# IR_detector_perf.net
KiCad netlist of a schematic drawn in EAGLE
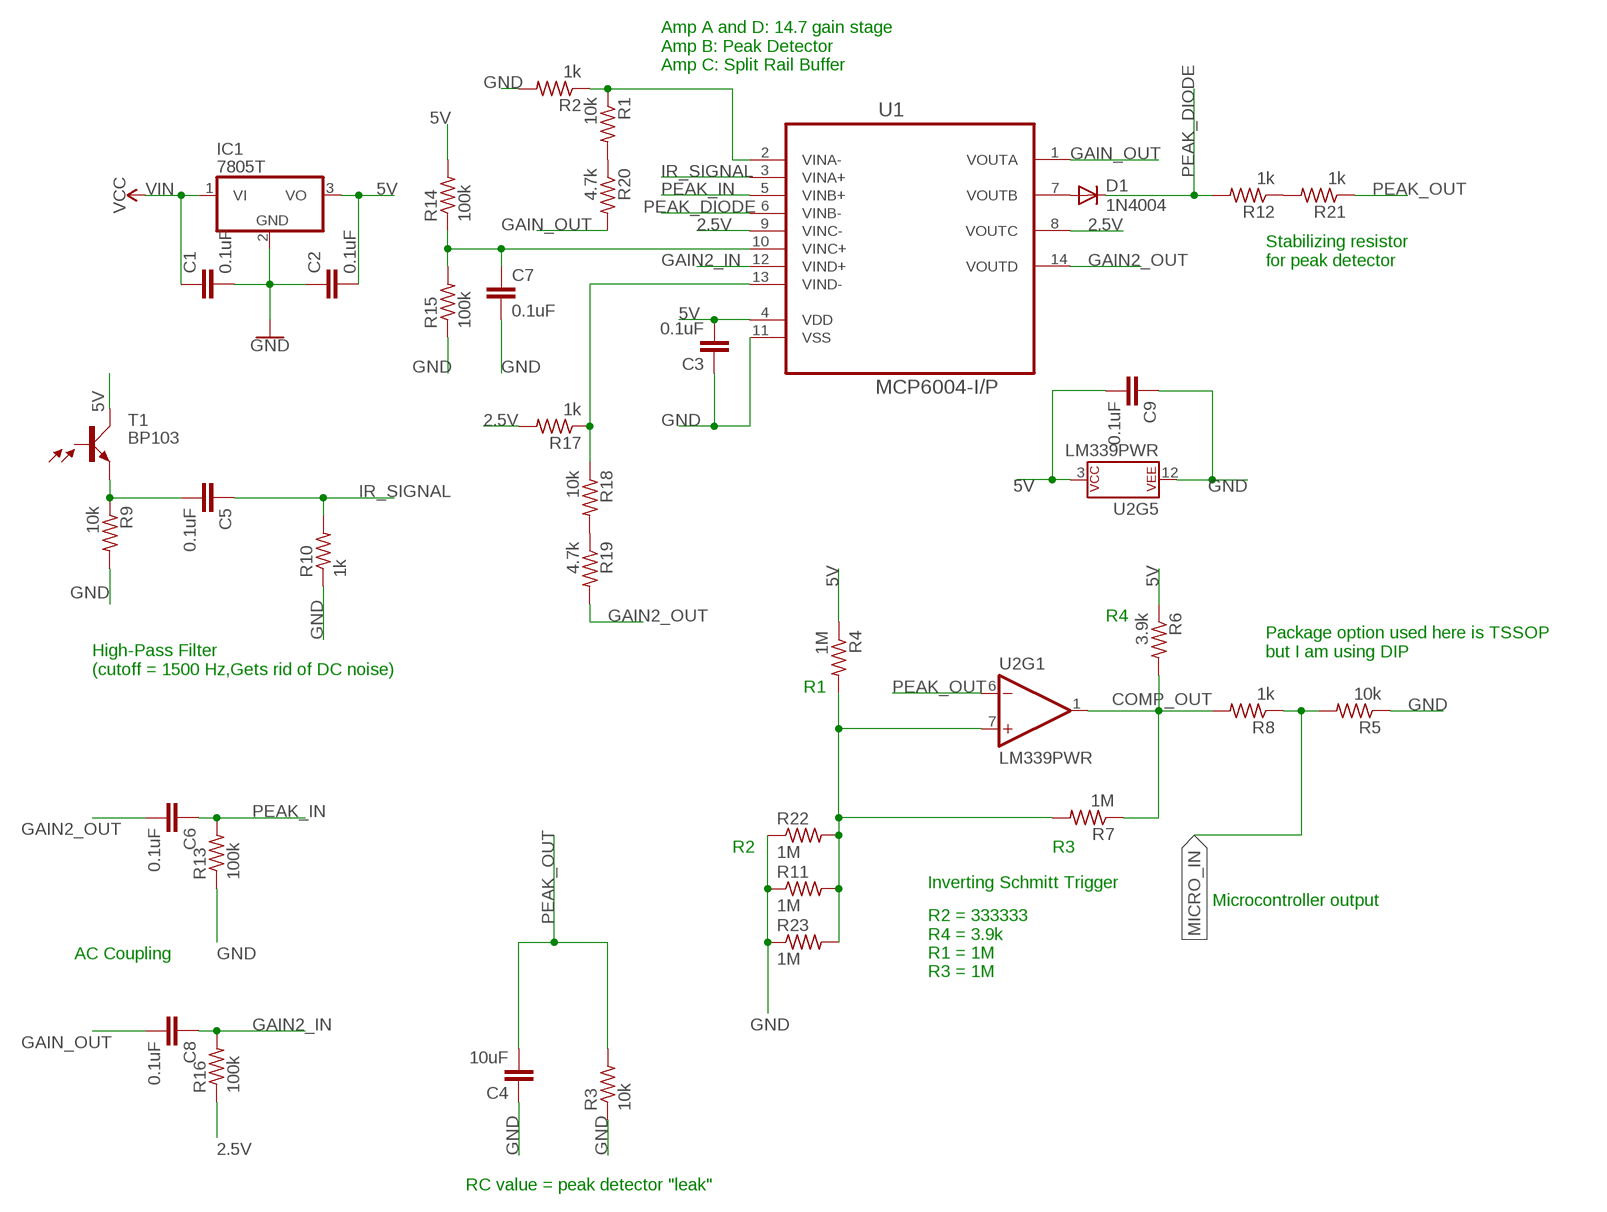
[diagram p0: schematic, sheet 1]

(export (version "E")
  (design (tool "Eeschema 10.0.6"))
  (components
    (comp (ref "C1")
      (value "0.1uF")
      (footprint "eagle-import:C025-024X044")
      (libsource (lib "eagle-import") (part "C-EU025-024X044"))
    )
    (comp (ref "C2")
      (value "0.1uF")
      (footprint "eagle-import:C025-024X044")
      (libsource (lib "eagle-import") (part "C-EU025-024X044"))
    )
    (comp (ref "C3")
      (value "0.1uF")
      (footprint "eagle-import:C025-024X044")
      (libsource (lib "eagle-import") (part "C-EU025-024X044"))
    )
    (comp (ref "C4")
      (value "10uF")
      (footprint "eagle-import:C025-024X044")
      (libsource (lib "eagle-import") (part "C-EU025-024X044"))
    )
    (comp (ref "C5")
      (value "0.1uF")
      (footprint "eagle-import:C025-024X044")
      (libsource (lib "eagle-import") (part "C-EU025-024X044"))
    )
    (comp (ref "C6")
      (value "0.1uF")
      (footprint "eagle-import:C025-024X044")
      (libsource (lib "eagle-import") (part "C-EU025-024X044"))
    )
    (comp (ref "C7")
      (value "0.1uF")
      (footprint "eagle-import:C025-024X044")
      (libsource (lib "eagle-import") (part "C-EU025-024X044"))
    )
    (comp (ref "C8")
      (value "0.1uF")
      (footprint "eagle-import:C025-024X044")
      (libsource (lib "eagle-import") (part "C-EU025-024X044"))
    )
    (comp (ref "C9")
      (value "0.1uF")
      (footprint "eagle-import:C025-024X044")
      (libsource (lib "eagle-import") (part "C-EU025-024X044"))
    )
    (comp (ref "D1")
      (value "1N4004")
      (footprint "eagle-import:DO41-10")
      (libsource (lib "eagle-import") (part "1N4004"))
    )
    (comp (ref "IC1")
      (value "7805T")
      (footprint "eagle-import:TO220H")
      (libsource (lib "eagle-import") (part "78T05"))
    )
    (comp (ref "R1")
      (value "10k")
      (footprint "eagle-import:0204V")
      (libsource (lib "eagle-import") (part "R-US_0204/2V"))
    )
    (comp (ref "R2")
      (value "1k")
      (footprint "eagle-import:0204V")
      (libsource (lib "eagle-import") (part "R-US_0204/2V"))
    )
    (comp (ref "R3")
      (value "10k")
      (footprint "eagle-import:0204V")
      (libsource (lib "eagle-import") (part "R-US_0204/2V"))
    )
    (comp (ref "R4")
      (value "1M")
      (footprint "eagle-import:0204V")
      (libsource (lib "eagle-import") (part "R-US_0204/2V"))
    )
    (comp (ref "R5")
      (value "10k")
      (footprint "eagle-import:0204V")
      (libsource (lib "eagle-import") (part "R-US_0204/2V"))
    )
    (comp (ref "R6")
      (value "3.9k")
      (footprint "eagle-import:0204V")
      (libsource (lib "eagle-import") (part "R-US_0204/2V"))
    )
    (comp (ref "R7")
      (value "1M")
      (footprint "eagle-import:0204V")
      (libsource (lib "eagle-import") (part "R-US_0204/2V"))
    )
    (comp (ref "R8")
      (value "1k")
      (footprint "eagle-import:0204V")
      (libsource (lib "eagle-import") (part "R-US_0204/2V"))
    )
    (comp (ref "R9")
      (value "10k")
      (footprint "eagle-import:0204V")
      (libsource (lib "eagle-import") (part "R-US_0204/2V"))
    )
    (comp (ref "R10")
      (value "1k")
      (footprint "eagle-import:0204V")
      (libsource (lib "eagle-import") (part "R-US_0204/2V"))
    )
    (comp (ref "R11")
      (value "1M")
      (footprint "eagle-import:0204V")
      (libsource (lib "eagle-import") (part "R-US_0204/2V"))
    )
    (comp (ref "R12")
      (value "1k")
      (footprint "eagle-import:0204V")
      (libsource (lib "eagle-import") (part "R-US_0204/2V"))
    )
    (comp (ref "R13")
      (value "100k")
      (footprint "eagle-import:0204V")
      (libsource (lib "eagle-import") (part "R-US_0204/2V"))
    )
    (comp (ref "R14")
      (value "100k")
      (footprint "eagle-import:0204V")
      (libsource (lib "eagle-import") (part "R-US_0204/2V"))
    )
    (comp (ref "R15")
      (value "100k")
      (footprint "eagle-import:0204V")
      (libsource (lib "eagle-import") (part "R-US_0204/2V"))
    )
    (comp (ref "R16")
      (value "100k")
      (footprint "eagle-import:0204V")
      (libsource (lib "eagle-import") (part "R-US_0204/2V"))
    )
    (comp (ref "R17")
      (value "1k")
      (footprint "eagle-import:0204V")
      (libsource (lib "eagle-import") (part "R-US_0204/2V"))
    )
    (comp (ref "R18")
      (value "10k")
      (footprint "eagle-import:0204V")
      (libsource (lib "eagle-import") (part "R-US_0204/2V"))
    )
    (comp (ref "R19")
      (value "4.7k")
      (footprint "eagle-import:0204V")
      (libsource (lib "eagle-import") (part "R-US_0204/2V"))
    )
    (comp (ref "R20")
      (value "4.7k")
      (footprint "eagle-import:0204V")
      (libsource (lib "eagle-import") (part "R-US_0204/2V"))
    )
    (comp (ref "R21")
      (value "1k")
      (footprint "eagle-import:0204V")
      (libsource (lib "eagle-import") (part "R-US_0204/2V"))
    )
    (comp (ref "R22")
      (value "1M")
      (footprint "eagle-import:0204V")
      (libsource (lib "eagle-import") (part "R-US_0204/2V"))
    )
    (comp (ref "R23")
      (value "1M")
      (footprint "eagle-import:0204V")
      (libsource (lib "eagle-import") (part "R-US_0204/2V"))
    )
    (comp (ref "T1")
      (value "BP103")
      (footprint "eagle-import:BP103")
      (libsource (lib "eagle-import") (part "BP103"))
    )
    (comp (ref "U1")
      (value "MCP6004-I/P")
      (footprint "eagle-import:DIP254P762X533-14")
      (libsource (lib "eagle-import") (part "MCP6004-I/P"))
    )
    (comp (ref "U2")
      (value "LM339PWR")
      (footprint "eagle-import:TSSOP-14")
      (libsource (lib "eagle-import") (part "LM339"))
    )
  )
  (nets
    (net (code "1") (name "/2.5V") (class "Default")
      (node (ref "R16") (pin "1") (pinfunction "1_1") (pintype "passive"))
      (node (ref "R17") (pin "2") (pinfunction "2_2") (pintype "passive"))
      (node (ref "U1") (pin "8") (pinfunction "VOUTC_8") (pintype "output"))
      (node (ref "U1") (pin "9") (pinfunction "VINC-_9") (pintype "input"))
    )
    (net (code "2") (name "/5V") (class "Default")
      (node (ref "C2") (pin "2") (pinfunction "2_2") (pintype "passive"))
      (node (ref "C3") (pin "2") (pinfunction "2_2") (pintype "passive"))
      (node (ref "C9") (pin "2") (pinfunction "2_2") (pintype "passive"))
      (node (ref "IC1") (pin "3") (pinfunction "VO_3") (pintype "passive"))
      (node (ref "R14") (pin "2") (pinfunction "2_2") (pintype "passive"))
      (node (ref "R4") (pin "1") (pinfunction "1_1") (pintype "passive"))
      (node (ref "R6") (pin "1") (pinfunction "1_1") (pintype "passive"))
      (node (ref "T1") (pin "C") (pinfunction "C_C") (pintype "passive"))
      (node (ref "U1") (pin "4") (pinfunction "VDD_4") (pintype "power_in"))
      (node (ref "U2") (pin "3") (pinfunction "P$V+_3") (pintype "bidirectional"))
    )
    (net (code "3") (name "/COMP_OUT") (class "Default")
      (node (ref "R6") (pin "2") (pinfunction "2_2") (pintype "passive"))
      (node (ref "R7") (pin "1") (pinfunction "1_1") (pintype "passive"))
      (node (ref "R8") (pin "2") (pinfunction "2_2") (pintype "passive"))
      (node (ref "U2") (pin "1") (pinfunction "OUT_1") (pintype "output"))
    )
    (net (code "4") (name "/GAIN2_IN") (class "Default")
      (node (ref "C8") (pin "1") (pinfunction "1_1") (pintype "passive"))
      (node (ref "R16") (pin "2") (pinfunction "2_2") (pintype "passive"))
      (node (ref "U1") (pin "12") (pinfunction "VIND+_12") (pintype "input"))
    )
    (net (code "5") (name "/GAIN2_OUT") (class "Default")
      (node (ref "C6") (pin "2") (pinfunction "2_2") (pintype "passive"))
      (node (ref "R19") (pin "2") (pinfunction "2_2") (pintype "passive"))
      (node (ref "U1") (pin "14") (pinfunction "VOUTD_14") (pintype "output"))
    )
    (net (code "6") (name "/GAIN_OUT") (class "Default")
      (node (ref "C8") (pin "2") (pinfunction "2_2") (pintype "passive"))
      (node (ref "R20") (pin "2") (pinfunction "2_2") (pintype "passive"))
      (node (ref "U1") (pin "1") (pinfunction "VOUTA_1") (pintype "output"))
    )
    (net (code "7") (name "/IR_SIGNAL") (class "Default")
      (node (ref "C5") (pin "1") (pinfunction "1_1") (pintype "passive"))
      (node (ref "R10") (pin "2") (pinfunction "2_2") (pintype "passive"))
      (node (ref "U1") (pin "3") (pinfunction "VINA+_3") (pintype "input"))
    )
    (net (code "8") (name "/PEAK_DIODE") (class "Default")
      (node (ref "D1") (pin "C") (pinfunction "C_C") (pintype "passive"))
      (node (ref "R12") (pin "2") (pinfunction "2_2") (pintype "passive"))
      (node (ref "U1") (pin "6") (pinfunction "VINB-_6") (pintype "input"))
    )
    (net (code "9") (name "/PEAK_IN") (class "Default")
      (node (ref "C6") (pin "1") (pinfunction "1_1") (pintype "passive"))
      (node (ref "R13") (pin "2") (pinfunction "2_2") (pintype "passive"))
      (node (ref "U1") (pin "5") (pinfunction "VINB+_5") (pintype "input"))
    )
    (net (code "10") (name "/PEAK_OUT") (class "Default")
      (node (ref "C4") (pin "2") (pinfunction "2_2") (pintype "passive"))
      (node (ref "R21") (pin "1") (pinfunction "1_1") (pintype "passive"))
      (node (ref "R3") (pin "2") (pinfunction "2_2") (pintype "passive"))
      (node (ref "U2") (pin "6") (pinfunction "-IN_6") (pintype "input"))
    )
    (net (code "11") (name "GND") (class "Default")
      (node (ref "C1") (pin "2") (pinfunction "2_2") (pintype "passive"))
      (node (ref "C2") (pin "1") (pinfunction "1_1") (pintype "passive"))
      (node (ref "C3") (pin "1") (pinfunction "1_1") (pintype "passive"))
      (node (ref "C4") (pin "1") (pinfunction "1_1") (pintype "passive"))
      (node (ref "C7") (pin "2") (pinfunction "2_2") (pintype "passive"))
      (node (ref "C9") (pin "1") (pinfunction "1_1") (pintype "passive"))
      (node (ref "IC1") (pin "2") (pinfunction "GND_2") (pintype "passive"))
      (node (ref "R10") (pin "1") (pinfunction "1_1") (pintype "passive"))
      (node (ref "R11") (pin "1") (pinfunction "1_1") (pintype "passive"))
      (node (ref "R13") (pin "1") (pinfunction "1_1") (pintype "passive"))
      (node (ref "R15") (pin "1") (pinfunction "1_1") (pintype "passive"))
      (node (ref "R2") (pin "2") (pinfunction "2_2") (pintype "passive"))
      (node (ref "R22") (pin "1") (pinfunction "1_1") (pintype "passive"))
      (node (ref "R23") (pin "1") (pinfunction "1_1") (pintype "passive"))
      (node (ref "R3") (pin "1") (pinfunction "1_1") (pintype "passive"))
      (node (ref "R5") (pin "1") (pinfunction "1_1") (pintype "passive"))
      (node (ref "R9") (pin "2") (pinfunction "2_2") (pintype "passive"))
      (node (ref "U1") (pin "11") (pinfunction "VSS_11") (pintype "passive"))
      (node (ref "U2") (pin "12") (pinfunction "P$V-_12") (pintype "bidirectional"))
    )
    (net (code "12") (name "MICRO_IN") (class "Default")
      (node (ref "R5") (pin "2") (pinfunction "2_2") (pintype "passive"))
      (node (ref "R8") (pin "1") (pinfunction "1_1") (pintype "passive"))
    )
    (net (code "13") (name "Net-(C5-Pad2)") (class "Default")
      (node (ref "C5") (pin "2") (pinfunction "2_2") (pintype "passive"))
      (node (ref "R9") (pin "1") (pinfunction "1_1") (pintype "passive"))
      (node (ref "T1") (pin "E") (pinfunction "E_E") (pintype "passive"))
    )
    (net (code "14") (name "Net-(R1-Pad2)") (class "Default")
      (node (ref "R1") (pin "2") (pinfunction "2_2") (pintype "passive"))
      (node (ref "R20") (pin "1") (pinfunction "1_1") (pintype "passive"))
    )
    (net (code "15") (name "Net-(R12-Pad1)") (class "Default")
      (node (ref "R12") (pin "1") (pinfunction "1_1") (pintype "passive"))
      (node (ref "R21") (pin "2") (pinfunction "2_2") (pintype "passive"))
    )
    (net (code "16") (name "Net-(R18-Pad2)") (class "Default")
      (node (ref "R18") (pin "2") (pinfunction "2_2") (pintype "passive"))
      (node (ref "R19") (pin "1") (pinfunction "1_1") (pintype "passive"))
    )
    (net (code "17") (name "Net-(U1-VINA-)") (class "Default")
      (node (ref "R1") (pin "1") (pinfunction "1_1") (pintype "passive"))
      (node (ref "R2") (pin "1") (pinfunction "1_1") (pintype "passive"))
      (node (ref "U1") (pin "2") (pinfunction "VINA-_2") (pintype "input"))
    )
    (net (code "18") (name "Net-(U1-VINC+)") (class "Default")
      (node (ref "C7") (pin "1") (pinfunction "1_1") (pintype "passive"))
      (node (ref "R14") (pin "1") (pinfunction "1_1") (pintype "passive"))
      (node (ref "R15") (pin "2") (pinfunction "2_2") (pintype "passive"))
      (node (ref "U1") (pin "10") (pinfunction "VINC+_10") (pintype "input"))
    )
    (net (code "19") (name "Net-(U1-VIND-)") (class "Default")
      (node (ref "R17") (pin "1") (pinfunction "1_1") (pintype "passive"))
      (node (ref "R18") (pin "1") (pinfunction "1_1") (pintype "passive"))
      (node (ref "U1") (pin "13") (pinfunction "VIND-_13") (pintype "input"))
    )
    (net (code "20") (name "Net-(U1-VOUTB)") (class "Default")
      (node (ref "D1") (pin "A") (pinfunction "A_A") (pintype "passive"))
      (node (ref "U1") (pin "7") (pinfunction "VOUTB_7") (pintype "output"))
    )
    (net (code "21") (name "Net-(U2A-+IN)") (class "Default")
      (node (ref "R11") (pin "2") (pinfunction "2_2") (pintype "passive"))
      (node (ref "R22") (pin "2") (pinfunction "2_2") (pintype "passive"))
      (node (ref "R23") (pin "2") (pinfunction "2_2") (pintype "passive"))
      (node (ref "R4") (pin "2") (pinfunction "2_2") (pintype "passive"))
      (node (ref "R7") (pin "2") (pinfunction "2_2") (pintype "passive"))
      (node (ref "U2") (pin "7") (pinfunction "+IN_7") (pintype "input"))
    )
    (net (code "22") (name "VCC") (class "Default")
      (node (ref "C1") (pin "1") (pinfunction "1_1") (pintype "passive"))
      (node (ref "IC1") (pin "1") (pinfunction "VI_1") (pintype "input"))
    )
    (net (code "23") (name "unconnected-(T1-PadB)") (class "Default")
      (node (ref "T1") (pin "B") (pinfunction "B_B") (pintype "passive"))
    )
  )
)
